# Input.net
KiCad netlist of a schematic drawn in Altium Designer
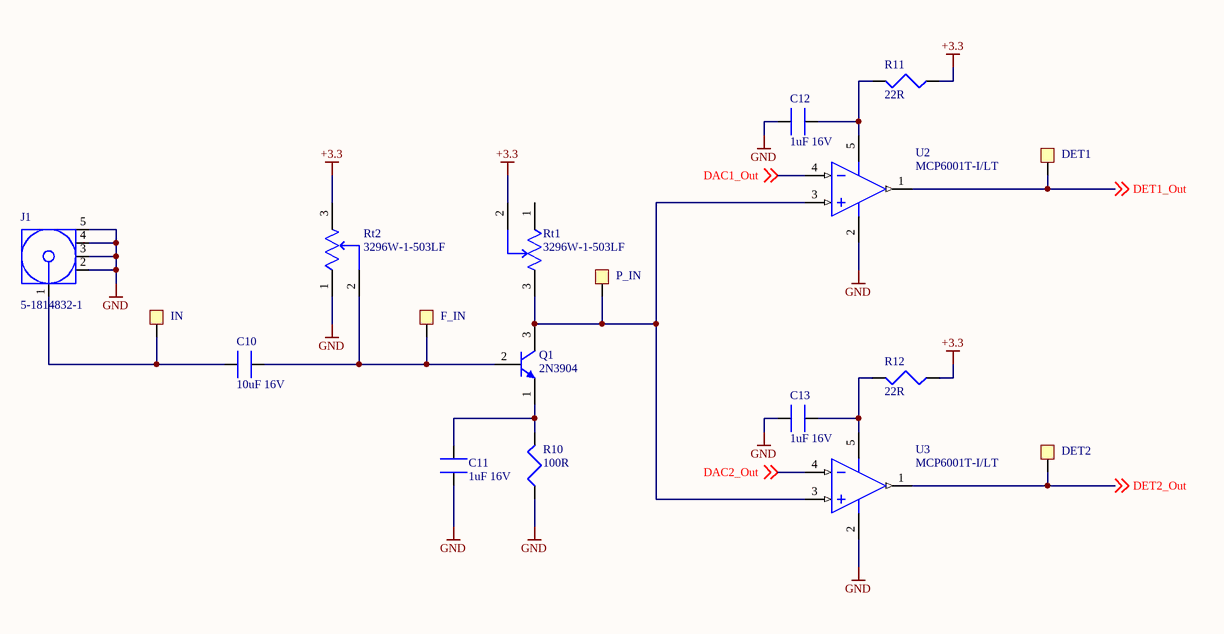
[diagram p0: Input.SchDoc]

(export (version "E")
  (design (tool "Eeschema 10.0.6"))
  (components
    (comp (ref "C10") (value "10uF 16V") (footprint "0805_C") (libsource (lib "Schlib1") (part "Cap")))
    (comp (ref "C11") (value "1uF 16V") (footprint "0805_C") (libsource (lib "Schlib1") (part "Cap")))
    (comp (ref "C12") (value "1uF 16V") (footprint "0805_C") (libsource (lib "Schlib1") (part "Cap")))
    (comp (ref "C13") (value "1uF 16V") (footprint "0805_C") (libsource (lib "Schlib1") (part "Cap")))
    (comp (ref "DET1") (value "Point") (footprint "Test_Point") (libsource (lib "Schlib1") (part "Point")))
    (comp (ref "DET2") (value "Point") (footprint "Test_Point") (libsource (lib "Schlib1") (part "Point")))
    (comp (ref "F_IN") (value "Point") (footprint "Test_Point") (libsource (lib "Schlib1") (part "Point")))
    (comp (ref "IN") (value "Point") (footprint "Test_Point") (libsource (lib "Schlib1") (part "Point")))
    (comp (ref "J1")
      (value "5-1814832-1")
      (footprint "TECO-5-1814832-1_V")
      (fields (field (name "MANUFACTURER") "TE Connectivity"))
      (libsource (lib "Altium Content Vault") (part "CN-S-4F-RF5"))
    )
    (comp (ref "P_IN") (value "Point") (footprint "Test_Point") (libsource (lib "Schlib1") (part "Point")))
    (comp (ref "Q1")
      (value "2N3904")
      (footprint "ONSC-TO-92-3-29-11")
      (description "General Purpose Transistor, NPN Silicon, 200 mA, 60 V, -55 to 150 degC, 3-Pin TO-92, RoHS, Bulk")
      (fields (field (name "MANUFACTURER") "ONSemiconductor"))
      (libsource (lib "Altium Content Vault") (part "BJT-NPN-EBC-3"))
    )
    (comp (ref "R10") (value "100R") (footprint "0805_R") (libsource (lib "Schlib1") (part "Res")))
    (comp (ref "R11") (value "22R") (footprint "0805_R") (libsource (lib "Schlib1") (part "Res")))
    (comp (ref "R12") (value "22R") (footprint "0805_R") (libsource (lib "Schlib1") (part "Res")))
    (comp (ref "Rt1")
      (value "3296W-1-503LF")
      (footprint "FP-3296W-MFG")
      (description "TRIMMER 50K OHM 0.5W PC PIN TOP")
      (fields
        (field (name "MANUFACTURER") "Bourns")
        (field (name "OCTOPART") "https://octopart.com/3296w-1-504lf-bourns-143884")
      )
      (libsource (lib "Altium Content Vault") (part "8d460c8a6f7ec10b1759d1b9c49aa93"))
    )
    (comp (ref "Rt2")
      (value "3296W-1-503LF")
      (footprint "FP-3296W-MFG")
      (description "TRIMMER 50K OHM 0.5W PC PIN TOP")
      (fields
        (field (name "MANUFACTURER") "Bourns")
        (field (name "OCTOPART") "https://octopart.com/3296w-1-504lf-bourns-143884")
      )
      (libsource (lib "Altium Content Vault") (part "8d460c8a6f7ec10b1759d1b9c49aa93"))
    )
    (comp (ref "U2")
      (value "MCP6001T-I/LT")
      (footprint "SC70-LT5_M")
      (description "1 MHz, Low-Power Operational Amplifier, 5-Pin SC-70, Industrial Temperature, Tape and Reel")
      (libsource (lib "Altium Content Vault") (part "AMP-OPA-MCP6001-SOT5"))
    )
    (comp (ref "U3")
      (value "MCP6001T-I/LT")
      (footprint "SC70-LT5_M")
      (description "1 MHz, Low-Power Operational Amplifier, 5-Pin SC-70, Industrial Temperature, Tape and Reel")
      (libsource (lib "Altium Content Vault") (part "AMP-OPA-MCP6001-SOT5"))
    )
  )
  (nets
    (net (code "1") (name "+3.3") (class "Default")
      (node (ref "R11") (pin "2") (pinfunction "2_2") (pintype "passive"))
      (node (ref "R12") (pin "2") (pinfunction "2_2") (pintype "passive"))
      (node (ref "Rt1") (pin "2") (pinfunction "WIPER_2") (pintype "passive"))
      (node (ref "Rt2") (pin "3") (pinfunction "CW_3") (pintype "passive"))
    )
    (net (code "2") (name "DAC1_Out") (class "Default")
      (node (ref "U2") (pin "4") (pinfunction "VIN-_4") (pintype "input"))
    )
    (net (code "3") (name "DAC2_Out") (class "Default")
      (node (ref "U3") (pin "4") (pinfunction "VIN-_4") (pintype "input"))
    )
    (net (code "4") (name "DET1_Out") (class "Default")
      (node (ref "DET1") (pin "1") (pinfunction "1_1") (pintype "passive"))
      (node (ref "U2") (pin "1") (pinfunction "VOUT_1") (pintype "output"))
    )
    (net (code "5") (name "DET2_Out") (class "Default")
      (node (ref "DET2") (pin "1") (pinfunction "1_1") (pintype "passive"))
      (node (ref "U3") (pin "1") (pinfunction "VOUT_1") (pintype "output"))
    )
    (net (code "6") (name "GND") (class "Default")
      (node (ref "C11") (pin "1") (pinfunction "1_1") (pintype "passive"))
      (node (ref "C12") (pin "2") (pinfunction "2_2") (pintype "passive"))
      (node (ref "C13") (pin "2") (pinfunction "2_2") (pintype "passive"))
      (node (ref "J1") (pin "2") (pinfunction "2_2") (pintype "passive"))
      (node (ref "J1") (pin "3") (pinfunction "3_3") (pintype "passive"))
      (node (ref "J1") (pin "4") (pinfunction "4_4") (pintype "passive"))
      (node (ref "J1") (pin "5") (pinfunction "5_5") (pintype "passive"))
      (node (ref "R10") (pin "2") (pinfunction "2_2") (pintype "passive"))
      (node (ref "Rt2") (pin "1") (pinfunction "CCW_1") (pintype "passive"))
      (node (ref "U2") (pin "2") (pinfunction "VSS_2") (pintype "power_in"))
      (node (ref "U3") (pin "2") (pinfunction "VSS_2") (pintype "power_in"))
    )
    (net (code "7") (name "Net-(C10-Pad1)") (class "Default")
      (node (ref "C10") (pin "1") (pinfunction "1_1") (pintype "passive"))
      (node (ref "IN") (pin "1") (pinfunction "1_1") (pintype "passive"))
      (node (ref "J1") (pin "1") (pinfunction "1_1") (pintype "passive"))
    )
    (net (code "8") (name "Net-(Q1-B)") (class "Default")
      (node (ref "C10") (pin "2") (pinfunction "2_2") (pintype "passive"))
      (node (ref "F_IN") (pin "1") (pinfunction "1_1") (pintype "passive"))
      (node (ref "Q1") (pin "2") (pinfunction "B_2") (pintype "passive"))
      (node (ref "Rt2") (pin "2") (pinfunction "WIPER_2") (pintype "passive"))
    )
    (net (code "9") (name "Net-(Q1-C)") (class "Default")
      (node (ref "P_IN") (pin "1") (pinfunction "1_1") (pintype "passive"))
      (node (ref "Q1") (pin "3") (pinfunction "C_3") (pintype "passive"))
      (node (ref "Rt1") (pin "3") (pinfunction "CW_3") (pintype "passive"))
      (node (ref "U2") (pin "3") (pinfunction "VIN+_3") (pintype "input"))
      (node (ref "U3") (pin "3") (pinfunction "VIN+_3") (pintype "input"))
    )
    (net (code "10") (name "Net-(Q1-E)") (class "Default")
      (node (ref "C11") (pin "2") (pinfunction "2_2") (pintype "passive"))
      (node (ref "Q1") (pin "1") (pinfunction "E_1") (pintype "passive"))
      (node (ref "R10") (pin "1") (pinfunction "1_1") (pintype "passive"))
    )
    (net (code "11") (name "Net-(U2-VDD)") (class "Default")
      (node (ref "C12") (pin "1") (pinfunction "1_1") (pintype "passive"))
      (node (ref "R11") (pin "1") (pinfunction "1_1") (pintype "passive"))
      (node (ref "U2") (pin "5") (pinfunction "VDD_5") (pintype "power_in"))
    )
    (net (code "12") (name "Net-(U3-VDD)") (class "Default")
      (node (ref "C13") (pin "1") (pinfunction "1_1") (pintype "passive"))
      (node (ref "R12") (pin "1") (pinfunction "1_1") (pintype "passive"))
      (node (ref "U3") (pin "5") (pinfunction "VDD_5") (pintype "power_in"))
    )
    (net (code "13") (name "unconnected-(Rt1-CCW-Pad1)") (class "Default")
      (node (ref "Rt1") (pin "1") (pinfunction "CCW_1") (pintype "passive"))
    )
  )
)
